# Reed_Switches.net
KiCad netlist of a schematic drawn in Altium Designer
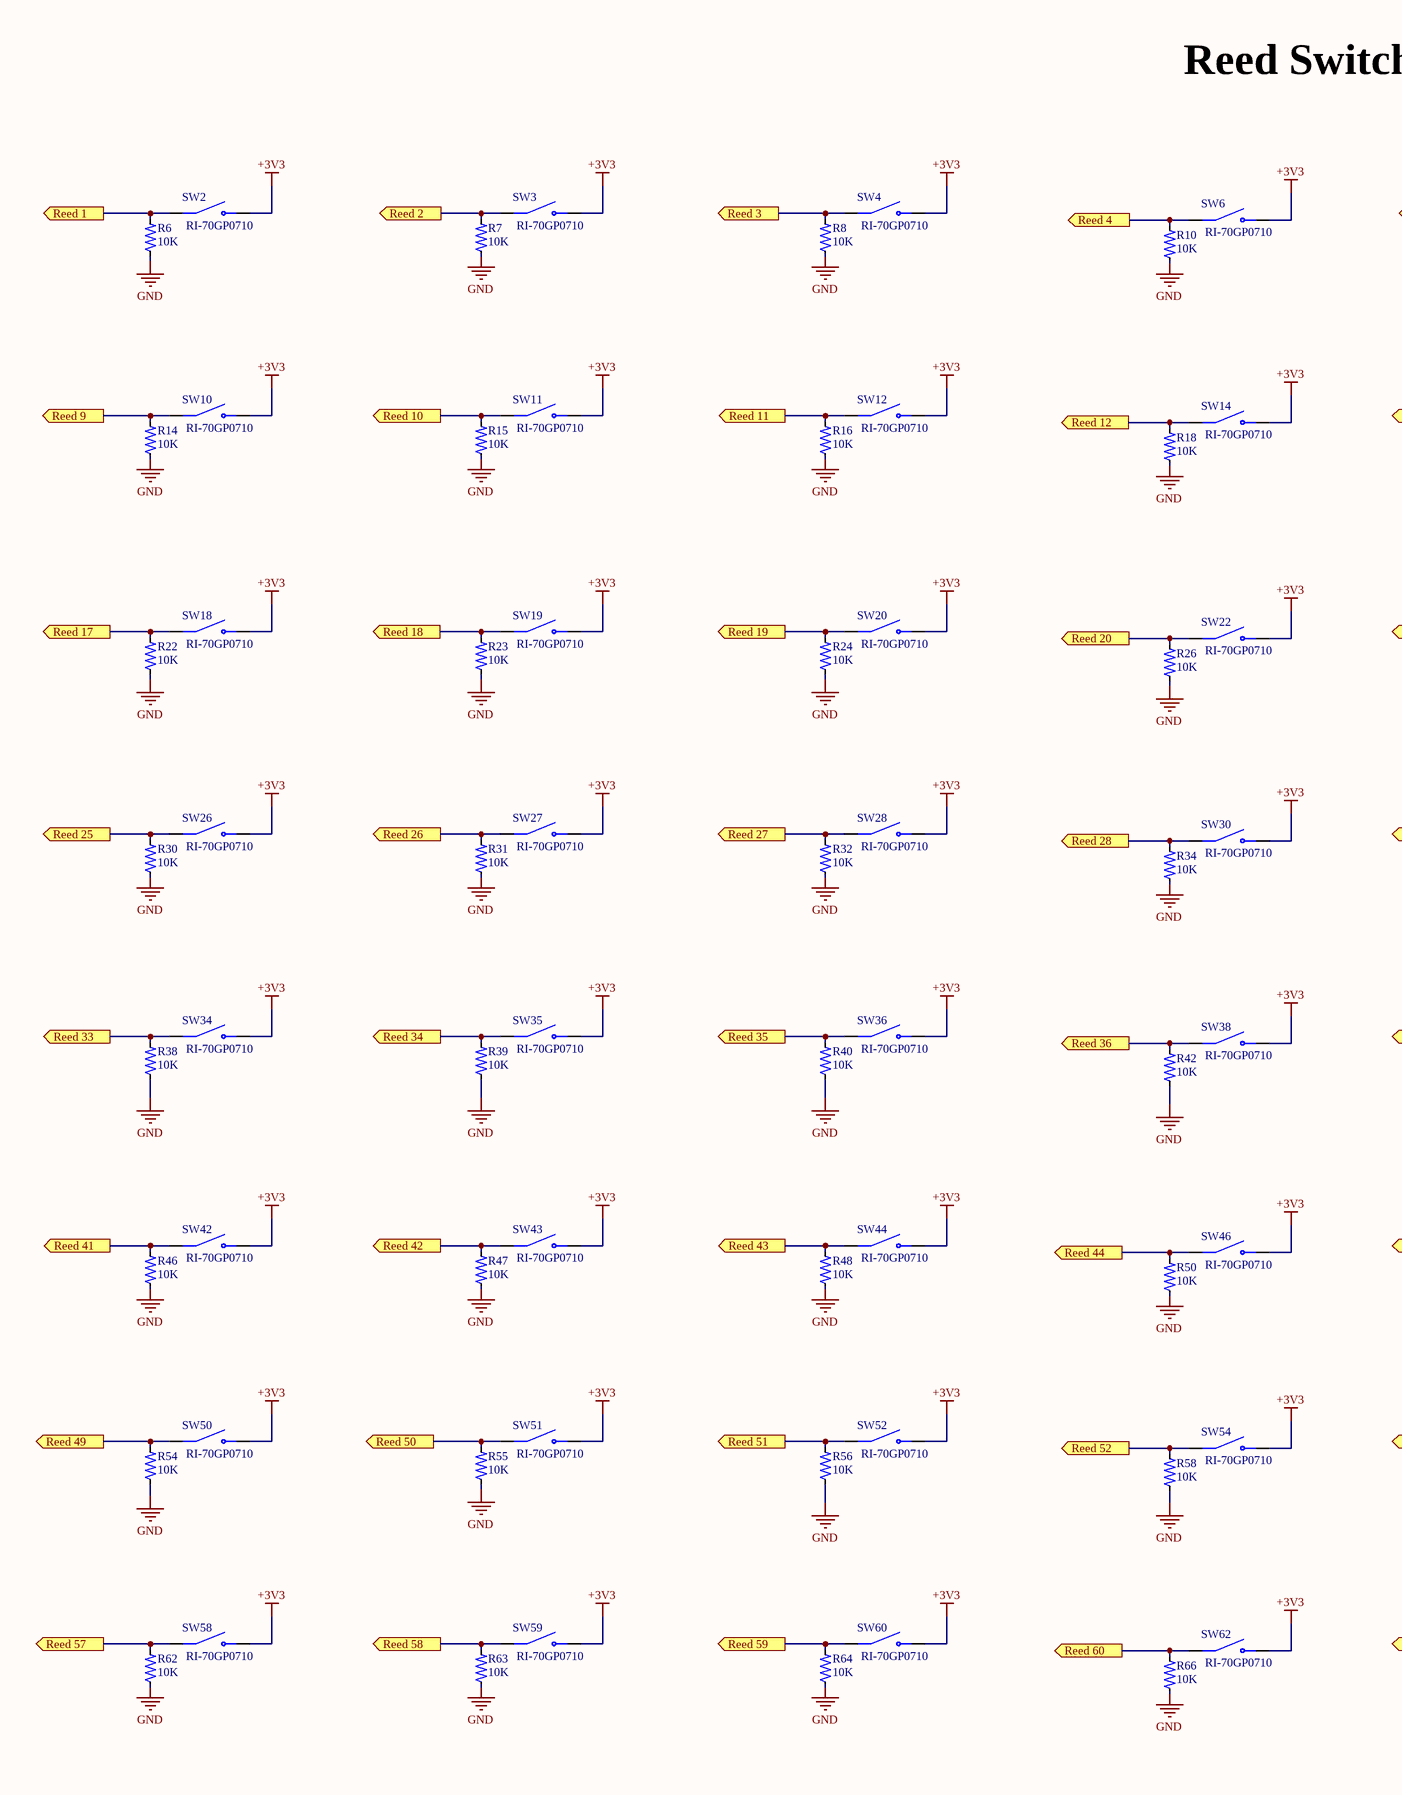
[diagram p0: Reed Switches.SchDoc, left]
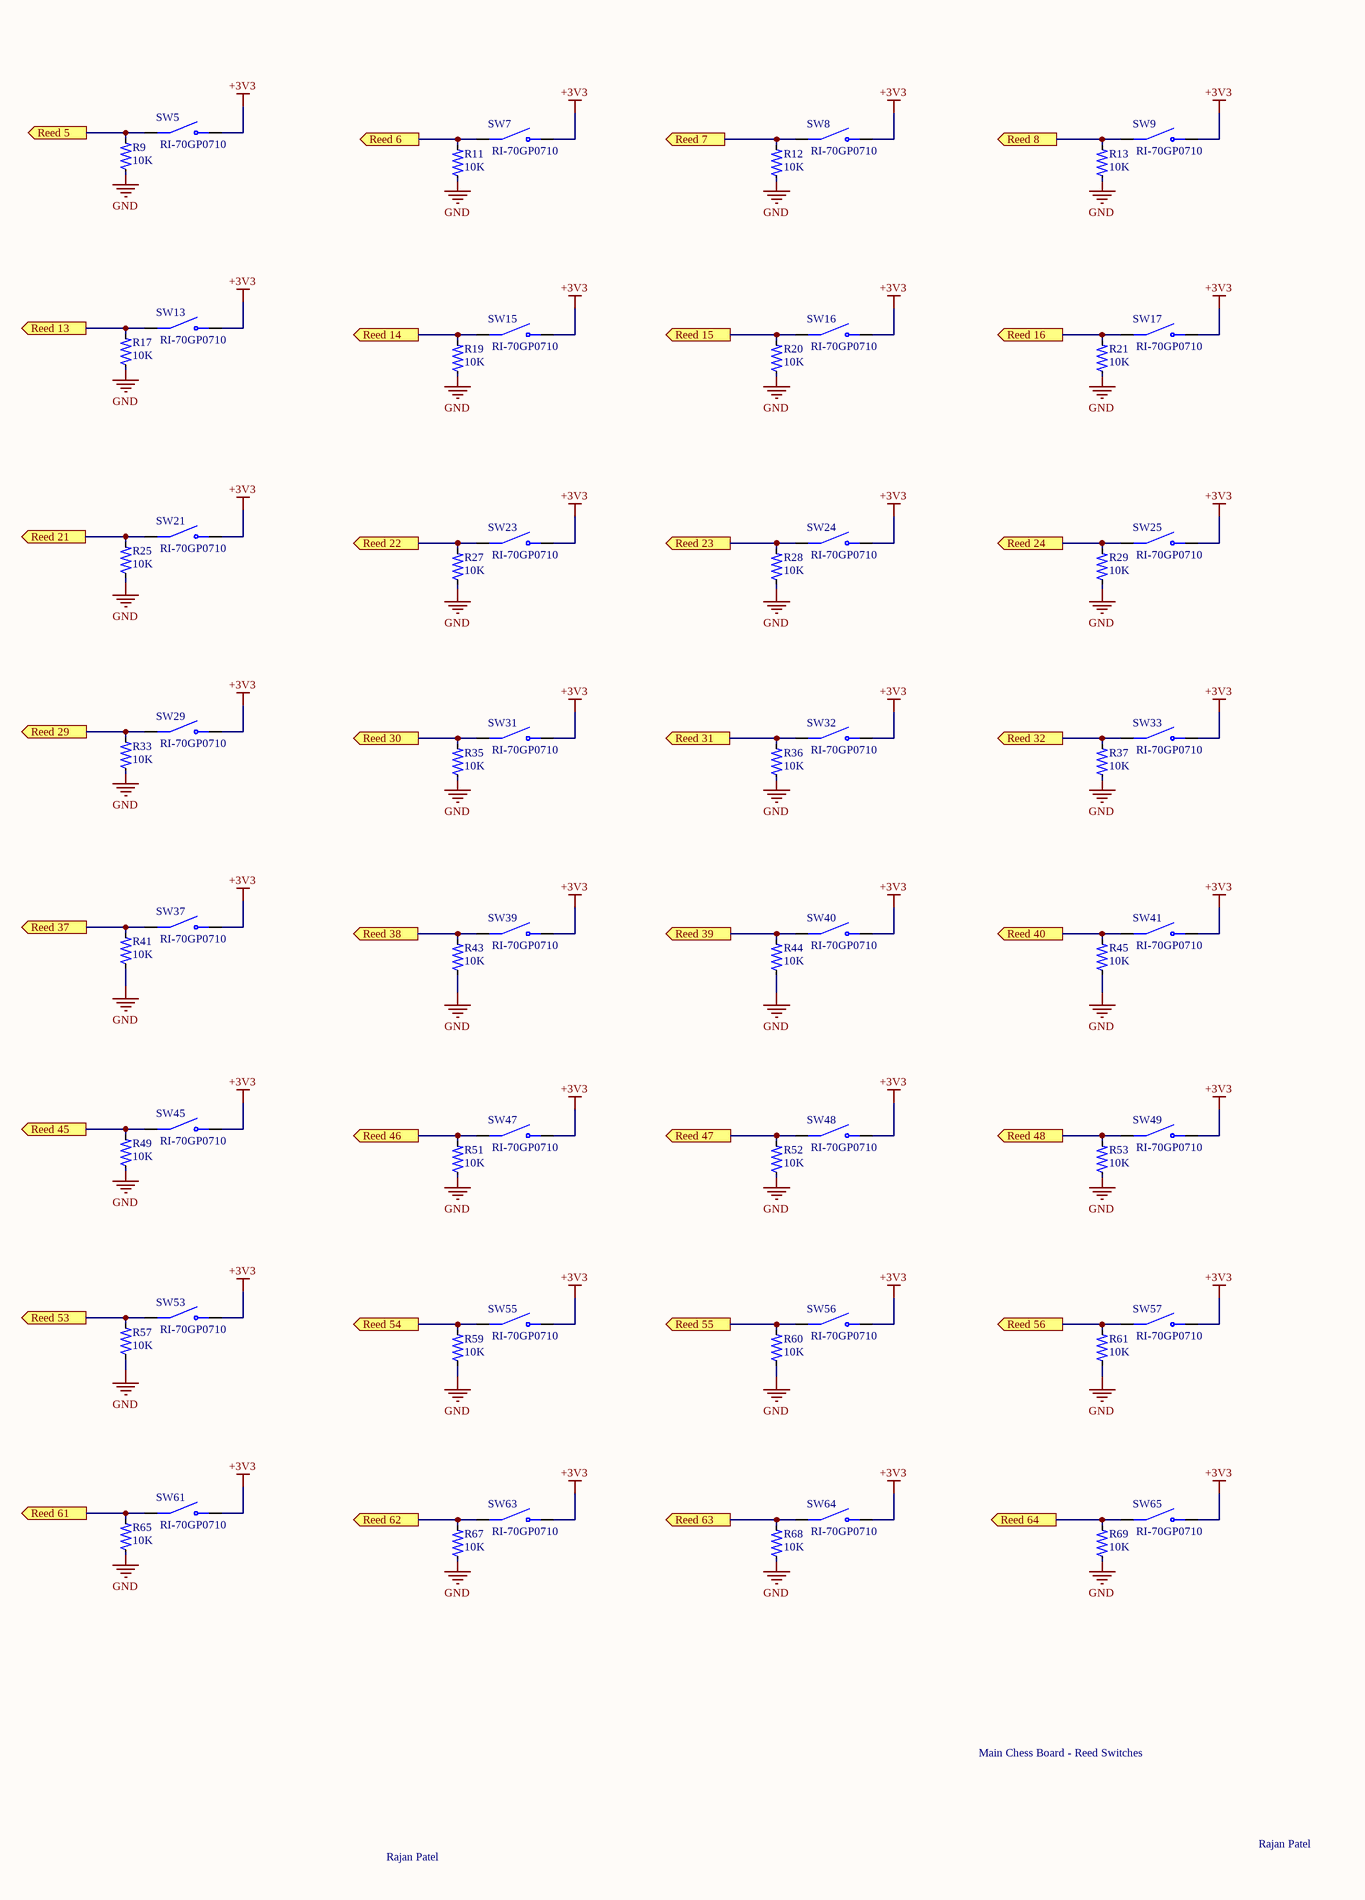
[diagram p1: Reed Switches.SchDoc, right]

(export (version "E")
  (design (tool "Eeschema 10.0.6"))
  (components
    (comp (ref "R6")
      (value "10K")
      (footprint "res 0805")
      (fields
        (field (name "MP") "2-2176053-2")
        (field (name "MF") "TE Connectivity")
        (field (name "TOLERANCE") "1%")
      )
      (libsource (lib "ChessBoardSchLib") (part "Resistor 0805"))
    )
    (comp (ref "R7")
      (value "10K")
      (footprint "res 0805")
      (fields
        (field (name "MP") "2-2176053-2")
        (field (name "MF") "TE Connectivity")
        (field (name "TOLERANCE") "1%")
      )
      (libsource (lib "ChessBoardSchLib") (part "Resistor 0805"))
    )
    (comp (ref "R8")
      (value "10K")
      (footprint "res 0805")
      (fields
        (field (name "MP") "2-2176053-2")
        (field (name "MF") "TE Connectivity")
        (field (name "TOLERANCE") "1%")
      )
      (libsource (lib "ChessBoardSchLib") (part "Resistor 0805"))
    )
    (comp (ref "R9")
      (value "10K")
      (footprint "res 0805")
      (fields
        (field (name "MP") "2-2176053-2")
        (field (name "MF") "TE Connectivity")
        (field (name "TOLERANCE") "1%")
      )
      (libsource (lib "ChessBoardSchLib") (part "Resistor 0805"))
    )
    (comp (ref "R10")
      (value "10K")
      (footprint "res 0805")
      (fields
        (field (name "MP") "2-2176053-2")
        (field (name "MF") "TE Connectivity")
        (field (name "TOLERANCE") "1%")
      )
      (libsource (lib "ChessBoardSchLib") (part "Resistor 0805"))
    )
    (comp (ref "R11")
      (value "10K")
      (footprint "res 0805")
      (fields
        (field (name "MP") "2-2176053-2")
        (field (name "MF") "TE Connectivity")
        (field (name "TOLERANCE") "1%")
      )
      (libsource (lib "ChessBoardSchLib") (part "Resistor 0805"))
    )
    (comp (ref "R12")
      (value "10K")
      (footprint "res 0805")
      (fields
        (field (name "MP") "2-2176053-2")
        (field (name "MF") "TE Connectivity")
        (field (name "TOLERANCE") "1%")
      )
      (libsource (lib "ChessBoardSchLib") (part "Resistor 0805"))
    )
    (comp (ref "R13")
      (value "10K")
      (footprint "res 0805")
      (fields
        (field (name "MP") "2-2176053-2")
        (field (name "MF") "TE Connectivity")
        (field (name "TOLERANCE") "1%")
      )
      (libsource (lib "ChessBoardSchLib") (part "Resistor 0805"))
    )
    (comp (ref "R14")
      (value "10K")
      (footprint "res 0805")
      (fields
        (field (name "MP") "2-2176053-2")
        (field (name "MF") "TE Connectivity")
        (field (name "TOLERANCE") "1%")
      )
      (libsource (lib "ChessBoardSchLib") (part "Resistor 0805"))
    )
    (comp (ref "R15")
      (value "10K")
      (footprint "res 0805")
      (fields
        (field (name "MP") "2-2176053-2")
        (field (name "MF") "TE Connectivity")
        (field (name "TOLERANCE") "1%")
      )
      (libsource (lib "ChessBoardSchLib") (part "Resistor 0805"))
    )
    (comp (ref "R16")
      (value "10K")
      (footprint "res 0805")
      (fields
        (field (name "MP") "2-2176053-2")
        (field (name "MF") "TE Connectivity")
        (field (name "TOLERANCE") "1%")
      )
      (libsource (lib "ChessBoardSchLib") (part "Resistor 0805"))
    )
    (comp (ref "R17")
      (value "10K")
      (footprint "res 0805")
      (fields
        (field (name "MP") "2-2176053-2")
        (field (name "MF") "TE Connectivity")
        (field (name "TOLERANCE") "1%")
      )
      (libsource (lib "ChessBoardSchLib") (part "Resistor 0805"))
    )
    (comp (ref "R18")
      (value "10K")
      (footprint "res 0805")
      (fields
        (field (name "MP") "2-2176053-2")
        (field (name "MF") "TE Connectivity")
        (field (name "TOLERANCE") "1%")
      )
      (libsource (lib "ChessBoardSchLib") (part "Resistor 0805"))
    )
    (comp (ref "R19")
      (value "10K")
      (footprint "res 0805")
      (fields
        (field (name "MP") "2-2176053-2")
        (field (name "MF") "TE Connectivity")
        (field (name "TOLERANCE") "1%")
      )
      (libsource (lib "ChessBoardSchLib") (part "Resistor 0805"))
    )
    (comp (ref "R20")
      (value "10K")
      (footprint "res 0805")
      (fields
        (field (name "MP") "2-2176053-2")
        (field (name "MF") "TE Connectivity")
        (field (name "TOLERANCE") "1%")
      )
      (libsource (lib "ChessBoardSchLib") (part "Resistor 0805"))
    )
    (comp (ref "R21")
      (value "10K")
      (footprint "res 0805")
      (fields
        (field (name "MP") "2-2176053-2")
        (field (name "MF") "TE Connectivity")
        (field (name "TOLERANCE") "1%")
      )
      (libsource (lib "ChessBoardSchLib") (part "Resistor 0805"))
    )
    (comp (ref "R22")
      (value "10K")
      (footprint "res 0805")
      (fields
        (field (name "MP") "2-2176053-2")
        (field (name "MF") "TE Connectivity")
        (field (name "TOLERANCE") "1%")
      )
      (libsource (lib "ChessBoardSchLib") (part "Resistor 0805"))
    )
    (comp (ref "R23")
      (value "10K")
      (footprint "res 0805")
      (fields
        (field (name "MP") "2-2176053-2")
        (field (name "MF") "TE Connectivity")
        (field (name "TOLERANCE") "1%")
      )
      (libsource (lib "ChessBoardSchLib") (part "Resistor 0805"))
    )
    (comp (ref "R24")
      (value "10K")
      (footprint "res 0805")
      (fields
        (field (name "MP") "2-2176053-2")
        (field (name "MF") "TE Connectivity")
        (field (name "TOLERANCE") "1%")
      )
      (libsource (lib "ChessBoardSchLib") (part "Resistor 0805"))
    )
    (comp (ref "R25")
      (value "10K")
      (footprint "res 0805")
      (fields
        (field (name "MP") "2-2176053-2")
        (field (name "MF") "TE Connectivity")
        (field (name "TOLERANCE") "1%")
      )
      (libsource (lib "ChessBoardSchLib") (part "Resistor 0805"))
    )
    (comp (ref "R26")
      (value "10K")
      (footprint "res 0805")
      (fields
        (field (name "MP") "2-2176053-2")
        (field (name "MF") "TE Connectivity")
        (field (name "TOLERANCE") "1%")
      )
      (libsource (lib "ChessBoardSchLib") (part "Resistor 0805"))
    )
    (comp (ref "R27")
      (value "10K")
      (footprint "res 0805")
      (fields
        (field (name "MP") "2-2176053-2")
        (field (name "MF") "TE Connectivity")
        (field (name "TOLERANCE") "1%")
      )
      (libsource (lib "ChessBoardSchLib") (part "Resistor 0805"))
    )
    (comp (ref "R28")
      (value "10K")
      (footprint "res 0805")
      (fields
        (field (name "MP") "2-2176053-2")
        (field (name "MF") "TE Connectivity")
        (field (name "TOLERANCE") "1%")
      )
      (libsource (lib "ChessBoardSchLib") (part "Resistor 0805"))
    )
    (comp (ref "R29")
      (value "10K")
      (footprint "res 0805")
      (fields
        (field (name "MP") "2-2176053-2")
        (field (name "MF") "TE Connectivity")
        (field (name "TOLERANCE") "1%")
      )
      (libsource (lib "ChessBoardSchLib") (part "Resistor 0805"))
    )
    (comp (ref "R30")
      (value "10K")
      (footprint "res 0805")
      (fields
        (field (name "MP") "2-2176053-2")
        (field (name "MF") "TE Connectivity")
        (field (name "TOLERANCE") "1%")
      )
      (libsource (lib "ChessBoardSchLib") (part "Resistor 0805"))
    )
    (comp (ref "R31")
      (value "10K")
      (footprint "res 0805")
      (fields
        (field (name "MP") "2-2176053-2")
        (field (name "MF") "TE Connectivity")
        (field (name "TOLERANCE") "1%")
      )
      (libsource (lib "ChessBoardSchLib") (part "Resistor 0805"))
    )
    (comp (ref "R32")
      (value "10K")
      (footprint "res 0805")
      (fields
        (field (name "MP") "2-2176053-2")
        (field (name "MF") "TE Connectivity")
        (field (name "TOLERANCE") "1%")
      )
      (libsource (lib "ChessBoardSchLib") (part "Resistor 0805"))
    )
    (comp (ref "R33")
      (value "10K")
      (footprint "res 0805")
      (fields
        (field (name "MP") "2-2176053-2")
        (field (name "MF") "TE Connectivity")
        (field (name "TOLERANCE") "1%")
      )
      (libsource (lib "ChessBoardSchLib") (part "Resistor 0805"))
    )
    (comp (ref "R34")
      (value "10K")
      (footprint "res 0805")
      (fields
        (field (name "MP") "2-2176053-2")
        (field (name "MF") "TE Connectivity")
        (field (name "TOLERANCE") "1%")
      )
      (libsource (lib "ChessBoardSchLib") (part "Resistor 0805"))
    )
    (comp (ref "R35")
      (value "10K")
      (footprint "res 0805")
      (fields
        (field (name "MP") "2-2176053-2")
        (field (name "MF") "TE Connectivity")
        (field (name "TOLERANCE") "1%")
      )
      (libsource (lib "ChessBoardSchLib") (part "Resistor 0805"))
    )
    (comp (ref "R36")
      (value "10K")
      (footprint "res 0805")
      (fields
        (field (name "MP") "2-2176053-2")
        (field (name "MF") "TE Connectivity")
        (field (name "TOLERANCE") "1%")
      )
      (libsource (lib "ChessBoardSchLib") (part "Resistor 0805"))
    )
    (comp (ref "R37")
      (value "10K")
      (footprint "res 0805")
      (fields
        (field (name "MP") "2-2176053-2")
        (field (name "MF") "TE Connectivity")
        (field (name "TOLERANCE") "1%")
      )
      (libsource (lib "ChessBoardSchLib") (part "Resistor 0805"))
    )
    (comp (ref "R38")
      (value "10K")
      (footprint "res 0805")
      (fields
        (field (name "MP") "2-2176053-2")
        (field (name "MF") "TE Connectivity")
        (field (name "TOLERANCE") "1%")
      )
      (libsource (lib "ChessBoardSchLib") (part "Resistor 0805"))
    )
    (comp (ref "R39")
      (value "10K")
      (footprint "res 0805")
      (fields
        (field (name "MP") "2-2176053-2")
        (field (name "MF") "TE Connectivity")
        (field (name "TOLERANCE") "1%")
      )
      (libsource (lib "ChessBoardSchLib") (part "Resistor 0805"))
    )
    (comp (ref "R40")
      (value "10K")
      (footprint "res 0805")
      (fields
        (field (name "MP") "2-2176053-2")
        (field (name "MF") "TE Connectivity")
        (field (name "TOLERANCE") "1%")
      )
      (libsource (lib "ChessBoardSchLib") (part "Resistor 0805"))
    )
    (comp (ref "R41")
      (value "10K")
      (footprint "res 0805")
      (fields
        (field (name "MP") "2-2176053-2")
        (field (name "MF") "TE Connectivity")
        (field (name "TOLERANCE") "1%")
      )
      (libsource (lib "ChessBoardSchLib") (part "Resistor 0805"))
    )
    (comp (ref "R42")
      (value "10K")
      (footprint "res 0805")
      (fields
        (field (name "MP") "2-2176053-2")
        (field (name "MF") "TE Connectivity")
        (field (name "TOLERANCE") "1%")
      )
      (libsource (lib "ChessBoardSchLib") (part "Resistor 0805"))
    )
    (comp (ref "R43")
      (value "10K")
      (footprint "res 0805")
      (fields
        (field (name "MP") "2-2176053-2")
        (field (name "MF") "TE Connectivity")
        (field (name "TOLERANCE") "1%")
      )
      (libsource (lib "ChessBoardSchLib") (part "Resistor 0805"))
    )
    (comp (ref "R44")
      (value "10K")
      (footprint "res 0805")
      (fields
        (field (name "MP") "2-2176053-2")
        (field (name "MF") "TE Connectivity")
        (field (name "TOLERANCE") "1%")
      )
      (libsource (lib "ChessBoardSchLib") (part "Resistor 0805"))
    )
    (comp (ref "R45")
      (value "10K")
      (footprint "res 0805")
      (fields
        (field (name "MP") "2-2176053-2")
        (field (name "MF") "TE Connectivity")
        (field (name "TOLERANCE") "1%")
      )
      (libsource (lib "ChessBoardSchLib") (part "Resistor 0805"))
    )
    (comp (ref "R46")
      (value "10K")
      (footprint "res 0805")
      (fields
        (field (name "MP") "2-2176053-2")
        (field (name "MF") "TE Connectivity")
        (field (name "TOLERANCE") "1%")
      )
      (libsource (lib "ChessBoardSchLib") (part "Resistor 0805"))
    )
    (comp (ref "R47")
      (value "10K")
      (footprint "res 0805")
      (fields
        (field (name "MP") "2-2176053-2")
        (field (name "MF") "TE Connectivity")
        (field (name "TOLERANCE") "1%")
      )
      (libsource (lib "ChessBoardSchLib") (part "Resistor 0805"))
    )
    (comp (ref "R48")
      (value "10K")
      (footprint "res 0805")
      (fields
        (field (name "MP") "2-2176053-2")
        (field (name "MF") "TE Connectivity")
        (field (name "TOLERANCE") "1%")
      )
      (libsource (lib "ChessBoardSchLib") (part "Resistor 0805"))
    )
    (comp (ref "R49")
      (value "10K")
      (footprint "res 0805")
      (fields
        (field (name "MP") "2-2176053-2")
        (field (name "MF") "TE Connectivity")
        (field (name "TOLERANCE") "1%")
      )
      (libsource (lib "ChessBoardSchLib") (part "Resistor 0805"))
    )
    (comp (ref "R50")
      (value "10K")
      (footprint "res 0805")
      (fields
        (field (name "MP") "2-2176053-2")
        (field (name "MF") "TE Connectivity")
        (field (name "TOLERANCE") "1%")
      )
      (libsource (lib "ChessBoardSchLib") (part "Resistor 0805"))
    )
    (comp (ref "R51")
      (value "10K")
      (footprint "res 0805")
      (fields
        (field (name "MP") "2-2176053-2")
        (field (name "MF") "TE Connectivity")
        (field (name "TOLERANCE") "1%")
      )
      (libsource (lib "ChessBoardSchLib") (part "Resistor 0805"))
    )
    (comp (ref "R52")
      (value "10K")
      (footprint "res 0805")
      (fields
        (field (name "MP") "2-2176053-2")
        (field (name "MF") "TE Connectivity")
        (field (name "TOLERANCE") "1%")
      )
      (libsource (lib "ChessBoardSchLib") (part "Resistor 0805"))
    )
    (comp (ref "R53")
      (value "10K")
      (footprint "res 0805")
      (fields
        (field (name "MP") "2-2176053-2")
        (field (name "MF") "TE Connectivity")
        (field (name "TOLERANCE") "1%")
      )
      (libsource (lib "ChessBoardSchLib") (part "Resistor 0805"))
    )
    (comp (ref "R54")
      (value "10K")
      (footprint "res 0805")
      (fields
        (field (name "MP") "2-2176053-2")
        (field (name "MF") "TE Connectivity")
        (field (name "TOLERANCE") "1%")
      )
      (libsource (lib "ChessBoardSchLib") (part "Resistor 0805"))
    )
    (comp (ref "R55")
      (value "10K")
      (footprint "res 0805")
      (fields
        (field (name "MP") "2-2176053-2")
        (field (name "MF") "TE Connectivity")
        (field (name "TOLERANCE") "1%")
      )
      (libsource (lib "ChessBoardSchLib") (part "Resistor 0805"))
    )
    (comp (ref "R56")
      (value "10K")
      (footprint "res 0805")
      (fields
        (field (name "MP") "2-2176053-2")
        (field (name "MF") "TE Connectivity")
        (field (name "TOLERANCE") "1%")
      )
      (libsource (lib "ChessBoardSchLib") (part "Resistor 0805"))
    )
    (comp (ref "R57")
      (value "10K")
      (footprint "res 0805")
      (fields
        (field (name "MP") "2-2176053-2")
        (field (name "MF") "TE Connectivity")
        (field (name "TOLERANCE") "1%")
      )
      (libsource (lib "ChessBoardSchLib") (part "Resistor 0805"))
    )
    (comp (ref "R58")
      (value "10K")
      (footprint "res 0805")
      (fields
        (field (name "MP") "2-2176053-2")
        (field (name "MF") "TE Connectivity")
        (field (name "TOLERANCE") "1%")
      )
      (libsource (lib "ChessBoardSchLib") (part "Resistor 0805"))
    )
    (comp (ref "R59")
      (value "10K")
      (footprint "res 0805")
      (fields
        (field (name "MP") "2-2176053-2")
        (field (name "MF") "TE Connectivity")
        (field (name "TOLERANCE") "1%")
      )
      (libsource (lib "ChessBoardSchLib") (part "Resistor 0805"))
    )
    (comp (ref "R60")
      (value "10K")
      (footprint "res 0805")
      (fields
        (field (name "MP") "2-2176053-2")
        (field (name "MF") "TE Connectivity")
        (field (name "TOLERANCE") "1%")
      )
      (libsource (lib "ChessBoardSchLib") (part "Resistor 0805"))
    )
    (comp (ref "R61")
      (value "10K")
      (footprint "res 0805")
      (fields
        (field (name "MP") "2-2176053-2")
        (field (name "MF") "TE Connectivity")
        (field (name "TOLERANCE") "1%")
      )
      (libsource (lib "ChessBoardSchLib") (part "Resistor 0805"))
    )
    (comp (ref "R62")
      (value "10K")
      (footprint "res 0805")
      (fields
        (field (name "MP") "2-2176053-2")
        (field (name "MF") "TE Connectivity")
        (field (name "TOLERANCE") "1%")
      )
      (libsource (lib "ChessBoardSchLib") (part "Resistor 0805"))
    )
    (comp (ref "R63")
      (value "10K")
      (footprint "res 0805")
      (fields
        (field (name "MP") "2-2176053-2")
        (field (name "MF") "TE Connectivity")
        (field (name "TOLERANCE") "1%")
      )
      (libsource (lib "ChessBoardSchLib") (part "Resistor 0805"))
    )
    (comp (ref "R64")
      (value "10K")
      (footprint "res 0805")
      (fields
        (field (name "MP") "2-2176053-2")
        (field (name "MF") "TE Connectivity")
        (field (name "TOLERANCE") "1%")
      )
      (libsource (lib "ChessBoardSchLib") (part "Resistor 0805"))
    )
    (comp (ref "R65")
      (value "10K")
      (footprint "res 0805")
      (fields
        (field (name "MP") "2-2176053-2")
        (field (name "MF") "TE Connectivity")
        (field (name "TOLERANCE") "1%")
      )
      (libsource (lib "ChessBoardSchLib") (part "Resistor 0805"))
    )
    (comp (ref "R66")
      (value "10K")
      (footprint "res 0805")
      (fields
        (field (name "MP") "2-2176053-2")
        (field (name "MF") "TE Connectivity")
        (field (name "TOLERANCE") "1%")
      )
      (libsource (lib "ChessBoardSchLib") (part "Resistor 0805"))
    )
    (comp (ref "R67")
      (value "10K")
      (footprint "res 0805")
      (fields
        (field (name "MP") "2-2176053-2")
        (field (name "MF") "TE Connectivity")
        (field (name "TOLERANCE") "1%")
      )
      (libsource (lib "ChessBoardSchLib") (part "Resistor 0805"))
    )
    (comp (ref "R68")
      (value "10K")
      (footprint "res 0805")
      (fields
        (field (name "MP") "2-2176053-2")
        (field (name "MF") "TE Connectivity")
        (field (name "TOLERANCE") "1%")
      )
      (libsource (lib "ChessBoardSchLib") (part "Resistor 0805"))
    )
    (comp (ref "R69")
      (value "10K")
      (footprint "res 0805")
      (fields
        (field (name "MP") "2-2176053-2")
        (field (name "MF") "TE Connectivity")
        (field (name "TOLERANCE") "1%")
      )
      (libsource (lib "ChessBoardSchLib") (part "Resistor 0805"))
    )
    (comp (ref "SW2")
      (value "RI-70GP0710")
      (footprint "RI-70GP0710")
      (description "Switch Reed Spst-no 500MA 120V")
      (fields (field (name "MANUFACTURER") "Comus"))
      (libsource (lib "ChessBoardSchLib") (part "RI-70GP0710"))
    )
    (comp (ref "SW3")
      (value "RI-70GP0710")
      (footprint "RI-70GP0710")
      (description "Switch Reed Spst-no 500MA 120V")
      (fields (field (name "MANUFACTURER") "Comus"))
      (libsource (lib "ChessBoardSchLib") (part "RI-70GP0710"))
    )
    (comp (ref "SW4")
      (value "RI-70GP0710")
      (footprint "RI-70GP0710")
      (description "Switch Reed Spst-no 500MA 120V")
      (fields (field (name "MANUFACTURER") "Comus"))
      (libsource (lib "ChessBoardSchLib") (part "RI-70GP0710"))
    )
    (comp (ref "SW5")
      (value "RI-70GP0710")
      (footprint "RI-70GP0710")
      (description "Switch Reed Spst-no 500MA 120V")
      (fields (field (name "MANUFACTURER") "Comus"))
      (libsource (lib "ChessBoardSchLib") (part "RI-70GP0710"))
    )
    (comp (ref "SW6")
      (value "RI-70GP0710")
      (footprint "RI-70GP0710")
      (description "Switch Reed Spst-no 500MA 120V")
      (fields (field (name "MANUFACTURER") "Comus"))
      (libsource (lib "ChessBoardSchLib") (part "RI-70GP0710"))
    )
    (comp (ref "SW7")
      (value "RI-70GP0710")
      (footprint "RI-70GP0710")
      (description "Switch Reed Spst-no 500MA 120V")
      (fields (field (name "MANUFACTURER") "Comus"))
      (libsource (lib "ChessBoardSchLib") (part "RI-70GP0710"))
    )
    (comp (ref "SW8")
      (value "RI-70GP0710")
      (footprint "RI-70GP0710")
      (description "Switch Reed Spst-no 500MA 120V")
      (fields (field (name "MANUFACTURER") "Comus"))
      (libsource (lib "ChessBoardSchLib") (part "RI-70GP0710"))
    )
    (comp (ref "SW9")
      (value "RI-70GP0710")
      (footprint "RI-70GP0710")
      (description "Switch Reed Spst-no 500MA 120V")
      (fields (field (name "MANUFACTURER") "Comus"))
      (libsource (lib "ChessBoardSchLib") (part "RI-70GP0710"))
    )
    (comp (ref "SW10")
      (value "RI-70GP0710")
      (footprint "RI-70GP0710")
      (description "Switch Reed Spst-no 500MA 120V")
      (fields (field (name "MANUFACTURER") "Comus"))
      (libsource (lib "ChessBoardSchLib") (part "RI-70GP0710"))
    )
    (comp (ref "SW11")
      (value "RI-70GP0710")
      (footprint "RI-70GP0710")
      (description "Switch Reed Spst-no 500MA 120V")
      (fields (field (name "MANUFACTURER") "Comus"))
      (libsource (lib "ChessBoardSchLib") (part "RI-70GP0710"))
    )
    (comp (ref "SW12")
      (value "RI-70GP0710")
      (footprint "RI-70GP0710")
      (description "Switch Reed Spst-no 500MA 120V")
      (fields (field (name "MANUFACTURER") "Comus"))
      (libsource (lib "ChessBoardSchLib") (part "RI-70GP0710"))
    )
    (comp (ref "SW13")
      (value "RI-70GP0710")
      (footprint "RI-70GP0710")
      (description "Switch Reed Spst-no 500MA 120V")
      (fields (field (name "MANUFACTURER") "Comus"))
      (libsource (lib "ChessBoardSchLib") (part "RI-70GP0710"))
    )
    (comp (ref "SW14")
      (value "RI-70GP0710")
      (footprint "RI-70GP0710")
      (description "Switch Reed Spst-no 500MA 120V")
      (fields (field (name "MANUFACTURER") "Comus"))
      (libsource (lib "ChessBoardSchLib") (part "RI-70GP0710"))
    )
    (comp (ref "SW15")
      (value "RI-70GP0710")
      (footprint "RI-70GP0710")
      (description "Switch Reed Spst-no 500MA 120V")
      (fields (field (name "MANUFACTURER") "Comus"))
      (libsource (lib "ChessBoardSchLib") (part "RI-70GP0710"))
    )
    (comp (ref "SW16")
      (value "RI-70GP0710")
      (footprint "RI-70GP0710")
      (description "Switch Reed Spst-no 500MA 120V")
      (fields (field (name "MANUFACTURER") "Comus"))
      (libsource (lib "ChessBoardSchLib") (part "RI-70GP0710"))
    )
    (comp (ref "SW17")
      (value "RI-70GP0710")
      (footprint "RI-70GP0710")
      (description "Switch Reed Spst-no 500MA 120V")
      (fields (field (name "MANUFACTURER") "Comus"))
      (libsource (lib "ChessBoardSchLib") (part "RI-70GP0710"))
    )
    (comp (ref "SW18")
      (value "RI-70GP0710")
      (footprint "RI-70GP0710")
      (description "Switch Reed Spst-no 500MA 120V")
      (fields (field (name "MANUFACTURER") "Comus"))
      (libsource (lib "ChessBoardSchLib") (part "RI-70GP0710"))
    )
    (comp (ref "SW19")
      (value "RI-70GP0710")
      (footprint "RI-70GP0710")
      (description "Switch Reed Spst-no 500MA 120V")
      (fields (field (name "MANUFACTURER") "Comus"))
      (libsource (lib "ChessBoardSchLib") (part "RI-70GP0710"))
    )
    (comp (ref "SW20")
      (value "RI-70GP0710")
      (footprint "RI-70GP0710")
      (description "Switch Reed Spst-no 500MA 120V")
      (fields (field (name "MANUFACTURER") "Comus"))
      (libsource (lib "ChessBoardSchLib") (part "RI-70GP0710"))
    )
    (comp (ref "SW21")
      (value "RI-70GP0710")
      (footprint "RI-70GP0710")
      (description "Switch Reed Spst-no 500MA 120V")
      (fields (field (name "MANUFACTURER") "Comus"))
      (libsource (lib "ChessBoardSchLib") (part "RI-70GP0710"))
    )
    (comp (ref "SW22")
      (value "RI-70GP0710")
      (footprint "RI-70GP0710")
      (description "Switch Reed Spst-no 500MA 120V")
      (fields (field (name "MANUFACTURER") "Comus"))
      (libsource (lib "ChessBoardSchLib") (part "RI-70GP0710"))
    )
    (comp (ref "SW23")
      (value "RI-70GP0710")
      (footprint "RI-70GP0710")
      (description "Switch Reed Spst-no 500MA 120V")
      (fields (field (name "MANUFACTURER") "Comus"))
      (libsource (lib "ChessBoardSchLib") (part "RI-70GP0710"))
    )
    (comp (ref "SW24")
      (value "RI-70GP0710")
      (footprint "RI-70GP0710")
      (description "Switch Reed Spst-no 500MA 120V")
      (fields (field (name "MANUFACTURER") "Comus"))
      (libsource (lib "ChessBoardSchLib") (part "RI-70GP0710"))
    )
    (comp (ref "SW25")
      (value "RI-70GP0710")
      (footprint "RI-70GP0710")
      (description "Switch Reed Spst-no 500MA 120V")
      (fields (field (name "MANUFACTURER") "Comus"))
      (libsource (lib "ChessBoardSchLib") (part "RI-70GP0710"))
    )
    (comp (ref "SW26")
      (value "RI-70GP0710")
      (footprint "RI-70GP0710")
      (description "Switch Reed Spst-no 500MA 120V")
      (fields (field (name "MANUFACTURER") "Comus"))
      (libsource (lib "ChessBoardSchLib") (part "RI-70GP0710"))
    )
    (comp (ref "SW27")
      (value "RI-70GP0710")
      (footprint "RI-70GP0710")
      (description "Switch Reed Spst-no 500MA 120V")
      (fields (field (name "MANUFACTURER") "Comus"))
      (libsource (lib "ChessBoardSchLib") (part "RI-70GP0710"))
    )
    (comp (ref "SW28")
      (value "RI-70GP0710")
      (footprint "RI-70GP0710")
      (description "Switch Reed Spst-no 500MA 120V")
      (fields (field (name "MANUFACTURER") "Comus"))
      (libsource (lib "ChessBoardSchLib") (part "RI-70GP0710"))
    )
    (comp (ref "SW29")
      (value "RI-70GP0710")
      (footprint "RI-70GP0710")
      (description "Switch Reed Spst-no 500MA 120V")
      (fields (field (name "MANUFACTURER") "Comus"))
      (libsource (lib "ChessBoardSchLib") (part "RI-70GP0710"))
    )
    (comp (ref "SW30")
      (value "RI-70GP0710")
      (footprint "RI-70GP0710")
      (description "Switch Reed Spst-no 500MA 120V")
      (fields (field (name "MANUFACTURER") "Comus"))
      (libsource (lib "ChessBoardSchLib") (part "RI-70GP0710"))
    )
    (comp (ref "SW31")
      (value "RI-70GP0710")
      (footprint "RI-70GP0710")
      (description "Switch Reed Spst-no 500MA 120V")
      (fields (field (name "MANUFACTURER") "Comus"))
      (libsource (lib "ChessBoardSchLib") (part "RI-70GP0710"))
    )
    (comp (ref "SW32")
      (value "RI-70GP0710")
      (footprint "RI-70GP0710")
      (description "Switch Reed Spst-no 500MA 120V")
      (fields (field (name "MANUFACTURER") "Comus"))
      (libsource (lib "ChessBoardSchLib") (part "RI-70GP0710"))
    )
    (comp (ref "SW33")
      (value "RI-70GP0710")
      (footprint "RI-70GP0710")
      (description "Switch Reed Spst-no 500MA 120V")
      (fields (field (name "MANUFACTURER") "Comus"))
      (libsource (lib "ChessBoardSchLib") (part "RI-70GP0710"))
    )
    (comp (ref "SW34")
      (value "RI-70GP0710")
      (footprint "RI-70GP0710")
      (description "Switch Reed Spst-no 500MA 120V")
      (fields (field (name "MANUFACTURER") "Comus"))
      (libsource (lib "ChessBoardSchLib") (part "RI-70GP0710"))
    )
    (comp (ref "SW35")
      (value "RI-70GP0710")
      (footprint "RI-70GP0710")
      (description "Switch Reed Spst-no 500MA 120V")
      (fields (field (name "MANUFACTURER") "Comus"))
      (libsource (lib "ChessBoardSchLib") (part "RI-70GP0710"))
    )
    (comp (ref "SW36")
      (value "RI-70GP0710")
      (footprint "RI-70GP0710")
      (description "Switch Reed Spst-no 500MA 120V")
      (fields (field (name "MANUFACTURER") "Comus"))
      (libsource (lib "ChessBoardSchLib") (part "RI-70GP0710"))
    )
    (comp (ref "SW37")
      (value "RI-70GP0710")
      (footprint "RI-70GP0710")
      (description "Switch Reed Spst-no 500MA 120V")
      (fields (field (name "MANUFACTURER") "Comus"))
      (libsource (lib "ChessBoardSchLib") (part "RI-70GP0710"))
    )
    (comp (ref "SW38")
      (value "RI-70GP0710")
      (footprint "RI-70GP0710")
      (description "Switch Reed Spst-no 500MA 120V")
      (fields (field (name "MANUFACTURER") "Comus"))
      (libsource (lib "ChessBoardSchLib") (part "RI-70GP0710"))
    )
    (comp (ref "SW39")
      (value "RI-70GP0710")
      (footprint "RI-70GP0710")
      (description "Switch Reed Spst-no 500MA 120V")
      (fields (field (name "MANUFACTURER") "Comus"))
      (libsource (lib "ChessBoardSchLib") (part "RI-70GP0710"))
    )
    (comp (ref "SW40")
      (value "RI-70GP0710")
      (footprint "RI-70GP0710")
      (description "Switch Reed Spst-no 500MA 120V")
      (fields (field (name "MANUFACTURER") "Comus"))
      (libsource (lib "ChessBoardSchLib") (part "RI-70GP0710"))
    )
    (comp (ref "SW41")
      (value "RI-70GP0710")
      (footprint "RI-70GP0710")
      (description "Switch Reed Spst-no 500MA 120V")
      (fields (field (name "MANUFACTURER") "Comus"))
      (libsource (lib "ChessBoardSchLib") (part "RI-70GP0710"))
    )
    (comp (ref "SW42")
      (value "RI-70GP0710")
      (footprint "RI-70GP0710")
      (description "Switch Reed Spst-no 500MA 120V")
      (fields (field (name "MANUFACTURER") "Comus"))
      (libsource (lib "ChessBoardSchLib") (part "RI-70GP0710"))
    )
    (comp (ref "SW43")
      (value "RI-70GP0710")
      (footprint "RI-70GP0710")
      (description "Switch Reed Spst-no 500MA 120V")
      (fields (field (name "MANUFACTURER") "Comus"))
      (libsource (lib "ChessBoardSchLib") (part "RI-70GP0710"))
    )
    (comp (ref "SW44")
      (value "RI-70GP0710")
      (footprint "RI-70GP0710")
      (description "Switch Reed Spst-no 500MA 120V")
      (fields (field (name "MANUFACTURER") "Comus"))
      (libsource (lib "ChessBoardSchLib") (part "RI-70GP0710"))
    )
    (comp (ref "SW45")
      (value "RI-70GP0710")
      (footprint "RI-70GP0710")
      (description "Switch Reed Spst-no 500MA 120V")
      (fields (field (name "MANUFACTURER") "Comus"))
      (libsource (lib "ChessBoardSchLib") (part "RI-70GP0710"))
    )
    (comp (ref "SW46")
      (value "RI-70GP0710")
      (footprint "RI-70GP0710")
      (description "Switch Reed Spst-no 500MA 120V")
      (fields (field (name "MANUFACTURER") "Comus"))
      (libsource (lib "ChessBoardSchLib") (part "RI-70GP0710"))
    )
    (comp (ref "SW47")
      (value "RI-70GP0710")
      (footprint "RI-70GP0710")
      (description "Switch Reed Spst-no 500MA 120V")
      (fields (field (name "MANUFACTURER") "Comus"))
      (libsource (lib "ChessBoardSchLib") (part "RI-70GP0710"))
    )
    (comp (ref "SW48")
      (value "RI-70GP0710")
      (footprint "RI-70GP0710")
      (description "Switch Reed Spst-no 500MA 120V")
      (fields (field (name "MANUFACTURER") "Comus"))
      (libsource (lib "ChessBoardSchLib") (part "RI-70GP0710"))
    )
    (comp (ref "SW49")
      (value "RI-70GP0710")
      (footprint "RI-70GP0710")
      (description "Switch Reed Spst-no 500MA 120V")
      (fields (field (name "MANUFACTURER") "Comus"))
      (libsource (lib "ChessBoardSchLib") (part "RI-70GP0710"))
    )
    (comp (ref "SW50")
      (value "RI-70GP0710")
      (footprint "RI-70GP0710")
      (description "Switch Reed Spst-no 500MA 120V")
      (fields (field (name "MANUFACTURER") "Comus"))
      (libsource (lib "ChessBoardSchLib") (part "RI-70GP0710"))
    )
    (comp (ref "SW51")
      (value "RI-70GP0710")
      (footprint "RI-70GP0710")
      (description "Switch Reed Spst-no 500MA 120V")
      (fields (field (name "MANUFACTURER") "Comus"))
      (libsource (lib "ChessBoardSchLib") (part "RI-70GP0710"))
    )
    (comp (ref "SW52")
      (value "RI-70GP0710")
      (footprint "RI-70GP0710")
      (description "Switch Reed Spst-no 500MA 120V")
      (fields (field (name "MANUFACTURER") "Comus"))
      (libsource (lib "ChessBoardSchLib") (part "RI-70GP0710"))
    )
    (comp (ref "SW53")
      (value "RI-70GP0710")
      (footprint "RI-70GP0710")
      (description "Switch Reed Spst-no 500MA 120V")
      (fields (field (name "MANUFACTURER") "Comus"))
      (libsource (lib "ChessBoardSchLib") (part "RI-70GP0710"))
    )
    (comp (ref "SW54")
      (value "RI-70GP0710")
      (footprint "RI-70GP0710")
      (description "Switch Reed Spst-no 500MA 120V")
      (fields (field (name "MANUFACTURER") "Comus"))
      (libsource (lib "ChessBoardSchLib") (part "RI-70GP0710"))
    )
    (comp (ref "SW55")
      (value "RI-70GP0710")
      (footprint "RI-70GP0710")
      (description "Switch Reed Spst-no 500MA 120V")
      (fields (field (name "MANUFACTURER") "Comus"))
      (libsource (lib "ChessBoardSchLib") (part "RI-70GP0710"))
    )
    (comp (ref "SW56")
      (value "RI-70GP0710")
      (footprint "RI-70GP0710")
      (description "Switch Reed Spst-no 500MA 120V")
      (fields (field (name "MANUFACTURER") "Comus"))
      (libsource (lib "ChessBoardSchLib") (part "RI-70GP0710"))
    )
    (comp (ref "SW57")
      (value "RI-70GP0710")
      (footprint "RI-70GP0710")
      (description "Switch Reed Spst-no 500MA 120V")
      (fields (field (name "MANUFACTURER") "Comus"))
      (libsource (lib "ChessBoardSchLib") (part "RI-70GP0710"))
    )
    (comp (ref "SW58")
      (value "RI-70GP0710")
      (footprint "RI-70GP0710")
      (description "Switch Reed Spst-no 500MA 120V")
      (fields (field (name "MANUFACTURER") "Comus"))
      (libsource (lib "ChessBoardSchLib") (part "RI-70GP0710"))
    )
    (comp (ref "SW59")
      (value "RI-70GP0710")
      (footprint "RI-70GP0710")
      (description "Switch Reed Spst-no 500MA 120V")
      (fields (field (name "MANUFACTURER") "Comus"))
      (libsource (lib "ChessBoardSchLib") (part "RI-70GP0710"))
    )
    (comp (ref "SW60")
      (value "RI-70GP0710")
      (footprint "RI-70GP0710")
      (description "Switch Reed Spst-no 500MA 120V")
      (fields (field (name "MANUFACTURER") "Comus"))
      (libsource (lib "ChessBoardSchLib") (part "RI-70GP0710"))
    )
    (comp (ref "SW61")
      (value "RI-70GP0710")
      (footprint "RI-70GP0710")
      (description "Switch Reed Spst-no 500MA 120V")
      (fields (field (name "MANUFACTURER") "Comus"))
      (libsource (lib "ChessBoardSchLib") (part "RI-70GP0710"))
    )
    (comp (ref "SW62")
      (value "RI-70GP0710")
      (footprint "RI-70GP0710")
      (description "Switch Reed Spst-no 500MA 120V")
      (fields (field (name "MANUFACTURER") "Comus"))
      (libsource (lib "ChessBoardSchLib") (part "RI-70GP0710"))
    )
    (comp (ref "SW63")
      (value "RI-70GP0710")
      (footprint "RI-70GP0710")
      (description "Switch Reed Spst-no 500MA 120V")
      (fields (field (name "MANUFACTURER") "Comus"))
      (libsource (lib "ChessBoardSchLib") (part "RI-70GP0710"))
    )
    (comp (ref "SW64")
      (value "RI-70GP0710")
      (footprint "RI-70GP0710")
      (description "Switch Reed Spst-no 500MA 120V")
      (fields (field (name "MANUFACTURER") "Comus"))
      (libsource (lib "ChessBoardSchLib") (part "RI-70GP0710"))
    )
    (comp (ref "SW65")
      (value "RI-70GP0710")
      (footprint "RI-70GP0710")
      (description "Switch Reed Spst-no 500MA 120V")
      (fields (field (name "MANUFACTURER") "Comus"))
      (libsource (lib "ChessBoardSchLib") (part "RI-70GP0710"))
    )
  )
  (nets
    (net (code "1") (name "+3V3") (class "Default")
      (node (ref "SW10") (pin "2") (pinfunction "NO_2") (pintype "passive"))
      (node (ref "SW11") (pin "2") (pinfunction "NO_2") (pintype "passive"))
      (node (ref "SW12") (pin "2") (pinfunction "NO_2") (pintype "passive"))
      (node (ref "SW13") (pin "2") (pinfunction "NO_2") (pintype "passive"))
      (node (ref "SW14") (pin "2") (pinfunction "NO_2") (pintype "passive"))
      (node (ref "SW15") (pin "2") (pinfunction "NO_2") (pintype "passive"))
      (node (ref "SW16") (pin "2") (pinfunction "NO_2") (pintype "passive"))
      (node (ref "SW17") (pin "2") (pinfunction "NO_2") (pintype "passive"))
      (node (ref "SW18") (pin "2") (pinfunction "NO_2") (pintype "passive"))
      (node (ref "SW19") (pin "2") (pinfunction "NO_2") (pintype "passive"))
      (node (ref "SW2") (pin "2") (pinfunction "NO_2") (pintype "passive"))
      (node (ref "SW20") (pin "2") (pinfunction "NO_2") (pintype "passive"))
      (node (ref "SW21") (pin "2") (pinfunction "NO_2") (pintype "passive"))
      (node (ref "SW22") (pin "2") (pinfunction "NO_2") (pintype "passive"))
      (node (ref "SW23") (pin "2") (pinfunction "NO_2") (pintype "passive"))
      (node (ref "SW24") (pin "2") (pinfunction "NO_2") (pintype "passive"))
      (node (ref "SW25") (pin "2") (pinfunction "NO_2") (pintype "passive"))
      (node (ref "SW26") (pin "2") (pinfunction "NO_2") (pintype "passive"))
      (node (ref "SW27") (pin "2") (pinfunction "NO_2") (pintype "passive"))
      (node (ref "SW28") (pin "2") (pinfunction "NO_2") (pintype "passive"))
      (node (ref "SW29") (pin "2") (pinfunction "NO_2") (pintype "passive"))
      (node (ref "SW3") (pin "2") (pinfunction "NO_2") (pintype "passive"))
      (node (ref "SW30") (pin "2") (pinfunction "NO_2") (pintype "passive"))
      (node (ref "SW31") (pin "2") (pinfunction "NO_2") (pintype "passive"))
      (node (ref "SW32") (pin "2") (pinfunction "NO_2") (pintype "passive"))
      (node (ref "SW33") (pin "2") (pinfunction "NO_2") (pintype "passive"))
      (node (ref "SW34") (pin "2") (pinfunction "NO_2") (pintype "passive"))
      (node (ref "SW35") (pin "2") (pinfunction "NO_2") (pintype "passive"))
      (node (ref "SW36") (pin "2") (pinfunction "NO_2") (pintype "passive"))
      (node (ref "SW37") (pin "2") (pinfunction "NO_2") (pintype "passive"))
      (node (ref "SW38") (pin "2") (pinfunction "NO_2") (pintype "passive"))
      (node (ref "SW39") (pin "2") (pinfunction "NO_2") (pintype "passive"))
      (node (ref "SW4") (pin "2") (pinfunction "NO_2") (pintype "passive"))
      (node (ref "SW40") (pin "2") (pinfunction "NO_2") (pintype "passive"))
      (node (ref "SW41") (pin "2") (pinfunction "NO_2") (pintype "passive"))
      (node (ref "SW42") (pin "2") (pinfunction "NO_2") (pintype "passive"))
      (node (ref "SW43") (pin "2") (pinfunction "NO_2") (pintype "passive"))
      (node (ref "SW44") (pin "2") (pinfunction "NO_2") (pintype "passive"))
      (node (ref "SW45") (pin "2") (pinfunction "NO_2") (pintype "passive"))
      (node (ref "SW46") (pin "2") (pinfunction "NO_2") (pintype "passive"))
      (node (ref "SW47") (pin "2") (pinfunction "NO_2") (pintype "passive"))
      (node (ref "SW48") (pin "2") (pinfunction "NO_2") (pintype "passive"))
      (node (ref "SW49") (pin "2") (pinfunction "NO_2") (pintype "passive"))
      (node (ref "SW5") (pin "2") (pinfunction "NO_2") (pintype "passive"))
      (node (ref "SW50") (pin "2") (pinfunction "NO_2") (pintype "passive"))
      (node (ref "SW51") (pin "2") (pinfunction "NO_2") (pintype "passive"))
      (node (ref "SW52") (pin "2") (pinfunction "NO_2") (pintype "passive"))
      (node (ref "SW53") (pin "2") (pinfunction "NO_2") (pintype "passive"))
      (node (ref "SW54") (pin "2") (pinfunction "NO_2") (pintype "passive"))
      (node (ref "SW55") (pin "2") (pinfunction "NO_2") (pintype "passive"))
      (node (ref "SW56") (pin "2") (pinfunction "NO_2") (pintype "passive"))
      (node (ref "SW57") (pin "2") (pinfunction "NO_2") (pintype "passive"))
      (node (ref "SW58") (pin "2") (pinfunction "NO_2") (pintype "passive"))
      (node (ref "SW59") (pin "2") (pinfunction "NO_2") (pintype "passive"))
      (node (ref "SW6") (pin "2") (pinfunction "NO_2") (pintype "passive"))
      (node (ref "SW60") (pin "2") (pinfunction "NO_2") (pintype "passive"))
      (node (ref "SW61") (pin "2") (pinfunction "NO_2") (pintype "passive"))
      (node (ref "SW62") (pin "2") (pinfunction "NO_2") (pintype "passive"))
      (node (ref "SW63") (pin "2") (pinfunction "NO_2") (pintype "passive"))
      (node (ref "SW64") (pin "2") (pinfunction "NO_2") (pintype "passive"))
      (node (ref "SW65") (pin "2") (pinfunction "NO_2") (pintype "passive"))
      (node (ref "SW7") (pin "2") (pinfunction "NO_2") (pintype "passive"))
      (node (ref "SW8") (pin "2") (pinfunction "NO_2") (pintype "passive"))
      (node (ref "SW9") (pin "2") (pinfunction "NO_2") (pintype "passive"))
    )
    (net (code "2") (name "/Reed 1") (class "Default")
      (node (ref "R6") (pin "2") (pinfunction "2_2") (pintype "passive"))
      (node (ref "SW2") (pin "1") (pinfunction "COM_1") (pintype "passive"))
    )
    (net (code "3") (name "/Reed 2") (class "Default")
      (node (ref "R7") (pin "2") (pinfunction "2_2") (pintype "passive"))
      (node (ref "SW3") (pin "1") (pinfunction "COM_1") (pintype "passive"))
    )
    (net (code "4") (name "/Reed 3") (class "Default")
      (node (ref "R8") (pin "2") (pinfunction "2_2") (pintype "passive"))
      (node (ref "SW4") (pin "1") (pinfunction "COM_1") (pintype "passive"))
    )
    (net (code "5") (name "/Reed 4") (class "Default")
      (node (ref "R10") (pin "2") (pinfunction "2_2") (pintype "passive"))
      (node (ref "SW6") (pin "1") (pinfunction "COM_1") (pintype "passive"))
    )
    (net (code "6") (name "/Reed 5") (class "Default")
      (node (ref "R9") (pin "2") (pinfunction "2_2") (pintype "passive"))
      (node (ref "SW5") (pin "1") (pinfunction "COM_1") (pintype "passive"))
    )
    (net (code "7") (name "/Reed 6") (class "Default")
      (node (ref "R11") (pin "2") (pinfunction "2_2") (pintype "passive"))
      (node (ref "SW7") (pin "1") (pinfunction "COM_1") (pintype "passive"))
    )
    (net (code "8") (name "/Reed 7") (class "Default")
      (node (ref "R12") (pin "2") (pinfunction "2_2") (pintype "passive"))
      (node (ref "SW8") (pin "1") (pinfunction "COM_1") (pintype "passive"))
    )
    (net (code "9") (name "/Reed 8") (class "Default")
      (node (ref "R13") (pin "2") (pinfunction "2_2") (pintype "passive"))
      (node (ref "SW9") (pin "1") (pinfunction "COM_1") (pintype "passive"))
    )
    (net (code "10") (name "/Reed 9") (class "Default")
      (node (ref "R14") (pin "2") (pinfunction "2_2") (pintype "passive"))
      (node (ref "SW10") (pin "1") (pinfunction "COM_1") (pintype "passive"))
    )
    (net (code "11") (name "/Reed 10") (class "Default")
      (node (ref "R15") (pin "2") (pinfunction "2_2") (pintype "passive"))
      (node (ref "SW11") (pin "1") (pinfunction "COM_1") (pintype "passive"))
    )
    (net (code "12") (name "/Reed 11") (class "Default")
      (node (ref "R16") (pin "2") (pinfunction "2_2") (pintype "passive"))
      (node (ref "SW12") (pin "1") (pinfunction "COM_1") (pintype "passive"))
    )
    (net (code "13") (name "/Reed 12") (class "Default")
      (node (ref "R18") (pin "2") (pinfunction "2_2") (pintype "passive"))
      (node (ref "SW14") (pin "1") (pinfunction "COM_1") (pintype "passive"))
    )
    (net (code "14") (name "/Reed 13") (class "Default")
      (node (ref "R17") (pin "2") (pinfunction "2_2") (pintype "passive"))
      (node (ref "SW13") (pin "1") (pinfunction "COM_1") (pintype "passive"))
    )
    (net (code "15") (name "/Reed 14") (class "Default")
      (node (ref "R19") (pin "2") (pinfunction "2_2") (pintype "passive"))
      (node (ref "SW15") (pin "1") (pinfunction "COM_1") (pintype "passive"))
    )
    (net (code "16") (name "/Reed 15") (class "Default")
      (node (ref "R20") (pin "2") (pinfunction "2_2") (pintype "passive"))
      (node (ref "SW16") (pin "1") (pinfunction "COM_1") (pintype "passive"))
    )
    (net (code "17") (name "/Reed 16") (class "Default")
      (node (ref "R21") (pin "2") (pinfunction "2_2") (pintype "passive"))
      (node (ref "SW17") (pin "1") (pinfunction "COM_1") (pintype "passive"))
    )
    (net (code "18") (name "/Reed 17") (class "Default")
      (node (ref "R22") (pin "2") (pinfunction "2_2") (pintype "passive"))
      (node (ref "SW18") (pin "1") (pinfunction "COM_1") (pintype "passive"))
    )
    (net (code "19") (name "/Reed 18") (class "Default")
      (node (ref "R23") (pin "2") (pinfunction "2_2") (pintype "passive"))
      (node (ref "SW19") (pin "1") (pinfunction "COM_1") (pintype "passive"))
    )
    (net (code "20") (name "/Reed 19") (class "Default")
      (node (ref "R24") (pin "2") (pinfunction "2_2") (pintype "passive"))
      (node (ref "SW20") (pin "1") (pinfunction "COM_1") (pintype "passive"))
    )
    (net (code "21") (name "/Reed 20") (class "Default")
      (node (ref "R26") (pin "2") (pinfunction "2_2") (pintype "passive"))
      (node (ref "SW22") (pin "1") (pinfunction "COM_1") (pintype "passive"))
    )
    (net (code "22") (name "/Reed 21") (class "Default")
      (node (ref "R25") (pin "2") (pinfunction "2_2") (pintype "passive"))
      (node (ref "SW21") (pin "1") (pinfunction "COM_1") (pintype "passive"))
    )
    (net (code "23") (name "/Reed 22") (class "Default")
      (node (ref "R27") (pin "2") (pinfunction "2_2") (pintype "passive"))
      (node (ref "SW23") (pin "1") (pinfunction "COM_1") (pintype "passive"))
    )
    (net (code "24") (name "/Reed 23") (class "Default")
      (node (ref "R28") (pin "2") (pinfunction "2_2") (pintype "passive"))
      (node (ref "SW24") (pin "1") (pinfunction "COM_1") (pintype "passive"))
    )
    (net (code "25") (name "/Reed 24") (class "Default")
      (node (ref "R29") (pin "2") (pinfunction "2_2") (pintype "passive"))
      (node (ref "SW25") (pin "1") (pinfunction "COM_1") (pintype "passive"))
    )
    (net (code "26") (name "/Reed 25") (class "Default")
      (node (ref "R30") (pin "2") (pinfunction "2_2") (pintype "passive"))
      (node (ref "SW26") (pin "1") (pinfunction "COM_1") (pintype "passive"))
    )
    (net (code "27") (name "/Reed 26") (class "Default")
      (node (ref "R31") (pin "2") (pinfunction "2_2") (pintype "passive"))
      (node (ref "SW27") (pin "1") (pinfunction "COM_1") (pintype "passive"))
    )
    (net (code "28") (name "/Reed 27") (class "Default")
      (node (ref "R32") (pin "2") (pinfunction "2_2") (pintype "passive"))
      (node (ref "SW28") (pin "1") (pinfunction "COM_1") (pintype "passive"))
    )
    (net (code "29") (name "/Reed 28") (class "Default")
      (node (ref "R34") (pin "2") (pinfunction "2_2") (pintype "passive"))
      (node (ref "SW30") (pin "1") (pinfunction "COM_1") (pintype "passive"))
    )
    (net (code "30") (name "/Reed 29") (class "Default")
      (node (ref "R33") (pin "2") (pinfunction "2_2") (pintype "passive"))
      (node (ref "SW29") (pin "1") (pinfunction "COM_1") (pintype "passive"))
    )
    (net (code "31") (name "/Reed 30") (class "Default")
      (node (ref "R35") (pin "2") (pinfunction "2_2") (pintype "passive"))
      (node (ref "SW31") (pin "1") (pinfunction "COM_1") (pintype "passive"))
    )
    (net (code "32") (name "/Reed 31") (class "Default")
      (node (ref "R36") (pin "2") (pinfunction "2_2") (pintype "passive"))
      (node (ref "SW32") (pin "1") (pinfunction "COM_1") (pintype "passive"))
    )
    (net (code "33") (name "/Reed 32") (class "Default")
      (node (ref "R37") (pin "2") (pinfunction "2_2") (pintype "passive"))
      (node (ref "SW33") (pin "1") (pinfunction "COM_1") (pintype "passive"))
    )
    (net (code "34") (name "/Reed 33") (class "Default")
      (node (ref "R38") (pin "2") (pinfunction "2_2") (pintype "passive"))
      (node (ref "SW34") (pin "1") (pinfunction "COM_1") (pintype "passive"))
    )
    (net (code "35") (name "/Reed 34") (class "Default")
      (node (ref "R39") (pin "2") (pinfunction "2_2") (pintype "passive"))
      (node (ref "SW35") (pin "1") (pinfunction "COM_1") (pintype "passive"))
    )
    (net (code "36") (name "/Reed 35") (class "Default")
      (node (ref "R40") (pin "2") (pinfunction "2_2") (pintype "passive"))
      (node (ref "SW36") (pin "1") (pinfunction "COM_1") (pintype "passive"))
    )
    (net (code "37") (name "/Reed 36") (class "Default")
      (node (ref "R42") (pin "2") (pinfunction "2_2") (pintype "passive"))
      (node (ref "SW38") (pin "1") (pinfunction "COM_1") (pintype "passive"))
    )
    (net (code "38") (name "/Reed 37") (class "Default")
      (node (ref "R41") (pin "2") (pinfunction "2_2") (pintype "passive"))
      (node (ref "SW37") (pin "1") (pinfunction "COM_1") (pintype "passive"))
    )
    (net (code "39") (name "/Reed 38") (class "Default")
      (node (ref "R43") (pin "2") (pinfunction "2_2") (pintype "passive"))
      (node (ref "SW39") (pin "1") (pinfunction "COM_1") (pintype "passive"))
    )
    (net (code "40") (name "/Reed 39") (class "Default")
      (node (ref "R44") (pin "2") (pinfunction "2_2") (pintype "passive"))
      (node (ref "SW40") (pin "1") (pinfunction "COM_1") (pintype "passive"))
    )
    (net (code "41") (name "/Reed 40") (class "Default")
      (node (ref "R45") (pin "2") (pinfunction "2_2") (pintype "passive"))
      (node (ref "SW41") (pin "1") (pinfunction "COM_1") (pintype "passive"))
    )
    (net (code "42") (name "/Reed 41") (class "Default")
      (node (ref "R46") (pin "2") (pinfunction "2_2") (pintype "passive"))
      (node (ref "SW42") (pin "1") (pinfunction "COM_1") (pintype "passive"))
    )
    (net (code "43") (name "/Reed 42") (class "Default")
      (node (ref "R47") (pin "2") (pinfunction "2_2") (pintype "passive"))
      (node (ref "SW43") (pin "1") (pinfunction "COM_1") (pintype "passive"))
    )
    (net (code "44") (name "/Reed 43") (class "Default")
      (node (ref "R48") (pin "2") (pinfunction "2_2") (pintype "passive"))
      (node (ref "SW44") (pin "1") (pinfunction "COM_1") (pintype "passive"))
    )
    (net (code "45") (name "/Reed 44") (class "Default")
      (node (ref "R50") (pin "2") (pinfunction "2_2") (pintype "passive"))
      (node (ref "SW46") (pin "1") (pinfunction "COM_1") (pintype "passive"))
    )
    (net (code "46") (name "/Reed 45") (class "Default")
      (node (ref "R49") (pin "2") (pinfunction "2_2") (pintype "passive"))
      (node (ref "SW45") (pin "1") (pinfunction "COM_1") (pintype "passive"))
    )
    (net (code "47") (name "/Reed 46") (class "Default")
      (node (ref "R51") (pin "2") (pinfunction "2_2") (pintype "passive"))
      (node (ref "SW47") (pin "1") (pinfunction "COM_1") (pintype "passive"))
    )
    (net (code "48") (name "/Reed 47") (class "Default")
      (node (ref "R52") (pin "2") (pinfunction "2_2") (pintype "passive"))
      (node (ref "SW48") (pin "1") (pinfunction "COM_1") (pintype "passive"))
    )
    (net (code "49") (name "/Reed 48") (class "Default")
      (node (ref "R53") (pin "2") (pinfunction "2_2") (pintype "passive"))
      (node (ref "SW49") (pin "1") (pinfunction "COM_1") (pintype "passive"))
    )
    (net (code "50") (name "/Reed 49") (class "Default")
      (node (ref "R54") (pin "2") (pinfunction "2_2") (pintype "passive"))
      (node (ref "SW50") (pin "1") (pinfunction "COM_1") (pintype "passive"))
    )
    (net (code "51") (name "/Reed 50") (class "Default")
      (node (ref "R55") (pin "2") (pinfunction "2_2") (pintype "passive"))
      (node (ref "SW51") (pin "1") (pinfunction "COM_1") (pintype "passive"))
    )
    (net (code "52") (name "/Reed 51") (class "Default")
      (node (ref "R56") (pin "2") (pinfunction "2_2") (pintype "passive"))
      (node (ref "SW52") (pin "1") (pinfunction "COM_1") (pintype "passive"))
    )
    (net (code "53") (name "/Reed 52") (class "Default")
      (node (ref "R58") (pin "2") (pinfunction "2_2") (pintype "passive"))
      (node (ref "SW54") (pin "1") (pinfunction "COM_1") (pintype "passive"))
    )
    (net (code "54") (name "/Reed 53") (class "Default")
      (node (ref "R57") (pin "2") (pinfunction "2_2") (pintype "passive"))
      (node (ref "SW53") (pin "1") (pinfunction "COM_1") (pintype "passive"))
    )
    (net (code "55") (name "/Reed 54") (class "Default")
      (node (ref "R59") (pin "2") (pinfunction "2_2") (pintype "passive"))
      (node (ref "SW55") (pin "1") (pinfunction "COM_1") (pintype "passive"))
    )
    (net (code "56") (name "/Reed 55") (class "Default")
      (node (ref "R60") (pin "2") (pinfunction "2_2") (pintype "passive"))
      (node (ref "SW56") (pin "1") (pinfunction "COM_1") (pintype "passive"))
    )
    (net (code "57") (name "/Reed 56") (class "Default")
      (node (ref "R61") (pin "2") (pinfunction "2_2") (pintype "passive"))
      (node (ref "SW57") (pin "1") (pinfunction "COM_1") (pintype "passive"))
    )
    (net (code "58") (name "/Reed 57") (class "Default")
      (node (ref "R62") (pin "2") (pinfunction "2_2") (pintype "passive"))
      (node (ref "SW58") (pin "1") (pinfunction "COM_1") (pintype "passive"))
    )
    (net (code "59") (name "/Reed 58") (class "Default")
      (node (ref "R63") (pin "2") (pinfunction "2_2") (pintype "passive"))
      (node (ref "SW59") (pin "1") (pinfunction "COM_1") (pintype "passive"))
    )
    (net (code "60") (name "/Reed 59") (class "Default")
      (node (ref "R64") (pin "2") (pinfunction "2_2") (pintype "passive"))
      (node (ref "SW60") (pin "1") (pinfunction "COM_1") (pintype "passive"))
    )
    (net (code "61") (name "/Reed 60") (class "Default")
      (node (ref "R66") (pin "2") (pinfunction "2_2") (pintype "passive"))
      (node (ref "SW62") (pin "1") (pinfunction "COM_1") (pintype "passive"))
    )
    (net (code "62") (name "/Reed 61") (class "Default")
      (node (ref "R65") (pin "2") (pinfunction "2_2") (pintype "passive"))
      (node (ref "SW61") (pin "1") (pinfunction "COM_1") (pintype "passive"))
    )
    (net (code "63") (name "/Reed 62") (class "Default")
      (node (ref "R67") (pin "2") (pinfunction "2_2") (pintype "passive"))
      (node (ref "SW63") (pin "1") (pinfunction "COM_1") (pintype "passive"))
    )
    (net (code "64") (name "/Reed 63") (class "Default")
      (node (ref "R68") (pin "2") (pinfunction "2_2") (pintype "passive"))
      (node (ref "SW64") (pin "1") (pinfunction "COM_1") (pintype "passive"))
    )
    (net (code "65") (name "/Reed 64") (class "Default")
      (node (ref "R69") (pin "2") (pinfunction "2_2") (pintype "passive"))
      (node (ref "SW65") (pin "1") (pinfunction "COM_1") (pintype "passive"))
    )
    (net (code "66") (name "GND") (class "Default")
      (node (ref "R10") (pin "1") (pinfunction "1_1") (pintype "passive"))
      (node (ref "R11") (pin "1") (pinfunction "1_1") (pintype "passive"))
      (node (ref "R12") (pin "1") (pinfunction "1_1") (pintype "passive"))
      (node (ref "R13") (pin "1") (pinfunction "1_1") (pintype "passive"))
      (node (ref "R14") (pin "1") (pinfunction "1_1") (pintype "passive"))
      (node (ref "R15") (pin "1") (pinfunction "1_1") (pintype "passive"))
      (node (ref "R16") (pin "1") (pinfunction "1_1") (pintype "passive"))
      (node (ref "R17") (pin "1") (pinfunction "1_1") (pintype "passive"))
      (node (ref "R18") (pin "1") (pinfunction "1_1") (pintype "passive"))
      (node (ref "R19") (pin "1") (pinfunction "1_1") (pintype "passive"))
      (node (ref "R20") (pin "1") (pinfunction "1_1") (pintype "passive"))
      (node (ref "R21") (pin "1") (pinfunction "1_1") (pintype "passive"))
      (node (ref "R22") (pin "1") (pinfunction "1_1") (pintype "passive"))
      (node (ref "R23") (pin "1") (pinfunction "1_1") (pintype "passive"))
      (node (ref "R24") (pin "1") (pinfunction "1_1") (pintype "passive"))
      (node (ref "R25") (pin "1") (pinfunction "1_1") (pintype "passive"))
      (node (ref "R26") (pin "1") (pinfunction "1_1") (pintype "passive"))
      (node (ref "R27") (pin "1") (pinfunction "1_1") (pintype "passive"))
      (node (ref "R28") (pin "1") (pinfunction "1_1") (pintype "passive"))
      (node (ref "R29") (pin "1") (pinfunction "1_1") (pintype "passive"))
      (node (ref "R30") (pin "1") (pinfunction "1_1") (pintype "passive"))
      (node (ref "R31") (pin "1") (pinfunction "1_1") (pintype "passive"))
      (node (ref "R32") (pin "1") (pinfunction "1_1") (pintype "passive"))
      (node (ref "R33") (pin "1") (pinfunction "1_1") (pintype "passive"))
      (node (ref "R34") (pin "1") (pinfunction "1_1") (pintype "passive"))
      (node (ref "R35") (pin "1") (pinfunction "1_1") (pintype "passive"))
      (node (ref "R36") (pin "1") (pinfunction "1_1") (pintype "passive"))
      (node (ref "R37") (pin "1") (pinfunction "1_1") (pintype "passive"))
      (node (ref "R38") (pin "1") (pinfunction "1_1") (pintype "passive"))
      (node (ref "R39") (pin "1") (pinfunction "1_1") (pintype "passive"))
      (node (ref "R40") (pin "1") (pinfunction "1_1") (pintype "passive"))
      (node (ref "R41") (pin "1") (pinfunction "1_1") (pintype "passive"))
      (node (ref "R42") (pin "1") (pinfunction "1_1") (pintype "passive"))
      (node (ref "R43") (pin "1") (pinfunction "1_1") (pintype "passive"))
      (node (ref "R44") (pin "1") (pinfunction "1_1") (pintype "passive"))
      (node (ref "R45") (pin "1") (pinfunction "1_1") (pintype "passive"))
      (node (ref "R46") (pin "1") (pinfunction "1_1") (pintype "passive"))
      (node (ref "R47") (pin "1") (pinfunction "1_1") (pintype "passive"))
      (node (ref "R48") (pin "1") (pinfunction "1_1") (pintype "passive"))
      (node (ref "R49") (pin "1") (pinfunction "1_1") (pintype "passive"))
      (node (ref "R50") (pin "1") (pinfunction "1_1") (pintype "passive"))
      (node (ref "R51") (pin "1") (pinfunction "1_1") (pintype "passive"))
      (node (ref "R52") (pin "1") (pinfunction "1_1") (pintype "passive"))
      (node (ref "R53") (pin "1") (pinfunction "1_1") (pintype "passive"))
      (node (ref "R54") (pin "1") (pinfunction "1_1") (pintype "passive"))
      (node (ref "R55") (pin "1") (pinfunction "1_1") (pintype "passive"))
      (node (ref "R56") (pin "1") (pinfunction "1_1") (pintype "passive"))
      (node (ref "R57") (pin "1") (pinfunction "1_1") (pintype "passive"))
      (node (ref "R58") (pin "1") (pinfunction "1_1") (pintype "passive"))
      (node (ref "R59") (pin "1") (pinfunction "1_1") (pintype "passive"))
      (node (ref "R6") (pin "1") (pinfunction "1_1") (pintype "passive"))
      (node (ref "R60") (pin "1") (pinfunction "1_1") (pintype "passive"))
      (node (ref "R61") (pin "1") (pinfunction "1_1") (pintype "passive"))
      (node (ref "R62") (pin "1") (pinfunction "1_1") (pintype "passive"))
      (node (ref "R63") (pin "1") (pinfunction "1_1") (pintype "passive"))
      (node (ref "R64") (pin "1") (pinfunction "1_1") (pintype "passive"))
      (node (ref "R65") (pin "1") (pinfunction "1_1") (pintype "passive"))
      (node (ref "R66") (pin "1") (pinfunction "1_1") (pintype "passive"))
      (node (ref "R67") (pin "1") (pinfunction "1_1") (pintype "passive"))
      (node (ref "R68") (pin "1") (pinfunction "1_1") (pintype "passive"))
      (node (ref "R69") (pin "1") (pinfunction "1_1") (pintype "passive"))
      (node (ref "R7") (pin "1") (pinfunction "1_1") (pintype "passive"))
      (node (ref "R8") (pin "1") (pinfunction "1_1") (pintype "passive"))
      (node (ref "R9") (pin "1") (pinfunction "1_1") (pintype "passive"))
    )
  )
)
